# FIT_TCM_P1V0.net
KiCad netlist of a schematic drawn in Altium Designer
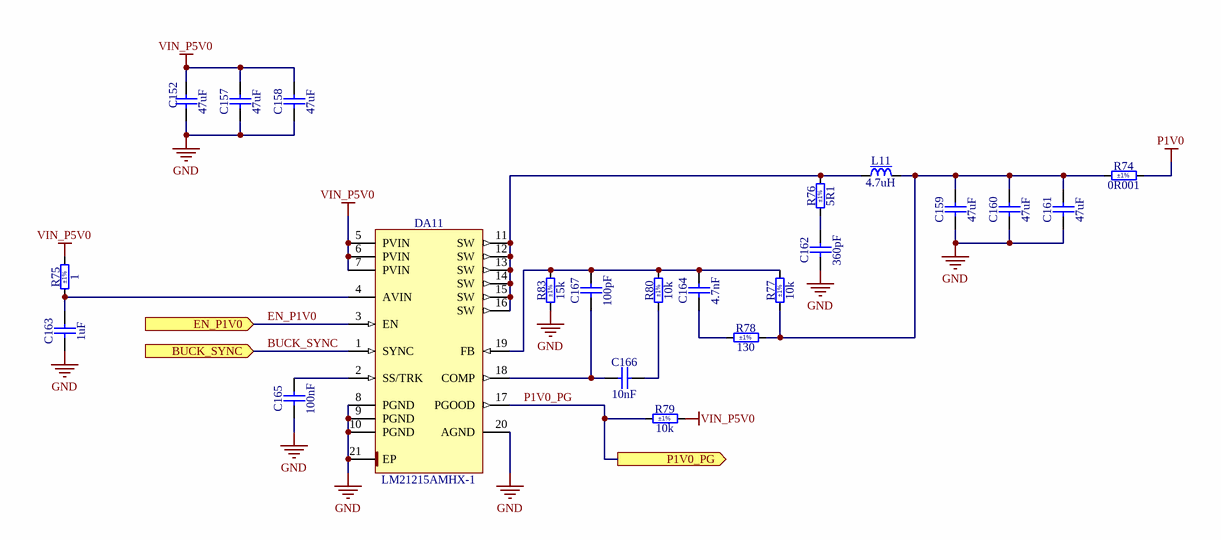
[diagram p0: FIT_TCM_P1V0.SchDoc]

(export (version "E")
  (design (tool "Eeschema 10.0.6"))
  (components
    (comp (ref "C152")
      (value "47uF")
      (footprint "CAPC3225X270N")
      (description "Non-polarised capacitor")
      (fields
        (field (name "PART NUMBER") "CC1210_47UF_16V_20%_X5R")
        (field (name "VOLTAGE") "16V")
        (field (name "AUTHOR") "CERN DEM MR")
      )
      (libsource (lib "Capacitors") (part "Capacitor - non polarized"))
    )
    (comp (ref "C157")
      (value "47uF")
      (footprint "CAPC3225X270N")
      (description "Non-polarised capacitor")
      (fields
        (field (name "PART NUMBER") "CC1210_47UF_16V_20%_X5R")
        (field (name "VOLTAGE") "16V")
        (field (name "AUTHOR") "CERN DEM MR")
      )
      (libsource (lib "Capacitors") (part "Capacitor - non polarized"))
    )
    (comp (ref "C158")
      (value "47uF")
      (footprint "CAPC3225X270N")
      (description "Non-polarised capacitor")
      (fields
        (field (name "PART NUMBER") "CC1210_47UF_16V_20%_X5R")
        (field (name "VOLTAGE") "16V")
        (field (name "AUTHOR") "CERN DEM MR")
      )
      (libsource (lib "Capacitors") (part "Capacitor - non polarized"))
    )
    (comp (ref "C159")
      (value "47uF")
      (footprint "CAPC3225X270N")
      (description "Non-polarised capacitor")
      (fields
        (field (name "PART NUMBER") "CC1210_47UF_16V_20%_X5R")
        (field (name "VOLTAGE") "16V")
        (field (name "AUTHOR") "CERN DEM MR")
      )
      (libsource (lib "Capacitors") (part "Capacitor - non polarized"))
    )
    (comp (ref "C160")
      (value "47uF")
      (footprint "CAPC3225X270N")
      (description "Non-polarised capacitor")
      (fields
        (field (name "PART NUMBER") "CC1210_47UF_16V_20%_X5R")
        (field (name "VOLTAGE") "16V")
        (field (name "AUTHOR") "CERN DEM MR")
      )
      (libsource (lib "Capacitors") (part "Capacitor - non polarized"))
    )
    (comp (ref "C161")
      (value "47uF")
      (footprint "CAPC3225X270N")
      (description "Non-polarised capacitor")
      (fields
        (field (name "PART NUMBER") "CC1210_47UF_16V_20%_X5R")
        (field (name "VOLTAGE") "16V")
        (field (name "AUTHOR") "CERN DEM MR")
      )
      (libsource (lib "Capacitors") (part "Capacitor - non polarized"))
    )
    (comp (ref "C162")
      (value "360pF")
      (footprint "CAPC2013X145N")
      (description "Non-polarised capacitor")
      (fields
        (field (name "PART NUMBER") "CC0805_360PF_50V_5%_C0G")
        (field (name "VOLTAGE") "50V")
        (field (name "AUTHOR") "CERN DEM HF")
      )
      (libsource (lib "Capacitors") (part "Capacitor - non polarized"))
    )
    (comp (ref "C163")
      (value "1uF")
      (footprint "CAPC2012X140N")
      (description "Non-polarised capacitor")
      (fields
        (field (name "PART NUMBER") "CC0805_1UF_25V_10%_X7R")
        (field (name "VOLTAGE") "25V")
        (field (name "AUTHOR") "CERN DEM JLC")
      )
      (libsource (lib "Capacitors") (part "Capacitor - non polarized"))
    )
    (comp (ref "C164")
      (value "4.7nF")
      (footprint "CAPC2012X135N")
      (description "Non-polarised capacitor")
      (fields
        (field (name "PART NUMBER") "CC0805_4.7NF_50V_10%_X7R")
        (field (name "VOLTAGE") "50V")
        (field (name "AUTHOR") "CERN DEM JLC")
      )
      (libsource (lib "Capacitors") (part "Capacitor - non polarized"))
    )
    (comp (ref "C165")
      (value "100nF")
      (footprint "CAPC2012X135N")
      (description "Non-polarised capacitor")
      (fields
        (field (name "PART NUMBER") "CC0805_100NF_50V_10%_X7R")
        (field (name "VOLTAGE") "50V")
        (field (name "AUTHOR") "CERN DEM JLC")
      )
      (libsource (lib "Capacitors") (part "Capacitor - non polarized"))
    )
    (comp (ref "C166")
      (value "10nF")
      (footprint "CAPC2012X135N")
      (description "Non-polarised capacitor")
      (fields
        (field (name "PART NUMBER") "CC0805_10NF_50V_10%_X7R")
        (field (name "VOLTAGE") "50V")
        (field (name "AUTHOR") "CERN DEM JLC")
      )
      (libsource (lib "Capacitors") (part "Capacitor - non polarized"))
    )
    (comp (ref "C167")
      (value "100pF")
      (footprint "CAPC2012X135N")
      (description "Non-polarised capacitor")
      (fields
        (field (name "PART NUMBER") "CC0805_100PF_50V_5%_NP0")
        (field (name "VOLTAGE") "50V")
        (field (name "AUTHOR") "CERN DEM JLC")
      )
      (libsource (lib "Capacitors") (part "Capacitor - non polarized"))
    )
    (comp (ref "DA11")
      (value "LM21215AMHX-1")
      (footprint "TEXAS_PWP0020AA")
      (description "2.95-V To 5.5-V, 12-A, Voltage-Mode Synchronous Buck Regulator with Frequency Synchronization")
      (fields (field (name "MANUFACTURER") "TEXAS INSTRUMENTS") (field (name "AUTHOR") "CERN DEM HF"))
      (libsource (lib "ICs And Semiconductors") (part "LM21215"))
    )
    (comp (ref "L11")
      (value "4.7uH")
      (footprint "INDM172170X700N")
      (description "Inductor With Core")
      (fields
        (field (name "PART NUMBER") "IND6767_4.7UH_20%_VISHAY_IHLP-6767GZ-11")
        (field (name "POWER") "30A")
        (field (name "AUTHOR") "CERN DEM HF")
      )
      (libsource (lib "Inductors & Transformers") (part "Inductor With Magnetic core"))
    )
    (comp (ref "R74")
      (value "0R001")
      (footprint "RESC_BOURNS_CRE2512_0R001-0R004")
      (description "Resistor - 1%")
      (fields
        (field (name "TOLERANCE") "±1%")
        (field (name "PART NUMBER") "R2512_0R001_1%_3W_50PPM_BOURNS_CRE2512")
        (field (name "POWER") "3W")
        (field (name "AUTHOR") "CERN DEM BC")
      )
      (libsource (lib "Resistors") (part "Resistor - 1%"))
    )
    (comp (ref "R75")
      (value "1")
      (footprint "RESC2012X60N")
      (description "Resistor - 1%")
      (fields
        (field (name "TOLERANCE") "±1%")
        (field (name "PART NUMBER") "R0805_1R_1%_0.125W_100PPM")
        (field (name "POWER") "0.125W")
        (field (name "AUTHOR") "CERN DEM HF")
      )
      (libsource (lib "Resistors") (part "Resistor - 1%"))
    )
    (comp (ref "R76")
      (value "5R1")
      (footprint "RESC2012X60N")
      (description "Resistor - 1%")
      (fields
        (field (name "TOLERANCE") "±1%")
        (field (name "PART NUMBER") "R0805_5R1_1%_0.125W_100PPM")
        (field (name "POWER") "0.125W")
        (field (name "AUTHOR") "CERN DEM HF")
      )
      (libsource (lib "Resistors") (part "Resistor - 1%"))
    )
    (comp (ref "R77")
      (value "10k")
      (footprint "RESC2012X60N")
      (description "Resistor - 1%")
      (fields
        (field (name "TOLERANCE") "±1%")
        (field (name "PART NUMBER") "R0805_10K_1%_0.125W_100PPM")
        (field (name "POWER") "0.125W")
        (field (name "AUTHOR") "CERN DEM JLC")
      )
      (libsource (lib "Resistors") (part "Resistor - 1%"))
    )
    (comp (ref "R78")
      (value "130")
      (footprint "RESC2012X60N")
      (description "Resistor - 1%")
      (fields
        (field (name "TOLERANCE") "±1%")
        (field (name "PART NUMBER") "R0805_130R_1%_0.125W_100PPM")
        (field (name "POWER") "0.125W")
        (field (name "AUTHOR") "CERN DEM JLC")
      )
      (libsource (lib "Resistors") (part "Resistor - 1%"))
    )
    (comp (ref "R79")
      (value "10k")
      (footprint "RESC2012X60N")
      (description "Resistor - 1%")
      (fields
        (field (name "TOLERANCE") "±1%")
        (field (name "PART NUMBER") "R0805_10K_1%_0.125W_100PPM")
        (field (name "POWER") "0.125W")
        (field (name "AUTHOR") "CERN DEM JLC")
      )
      (libsource (lib "Resistors") (part "Resistor - 1%"))
    )
    (comp (ref "R80")
      (value "10k")
      (footprint "RESC2012X60N")
      (description "Resistor - 1%")
      (fields
        (field (name "TOLERANCE") "±1%")
        (field (name "PART NUMBER") "R0805_10K_1%_0.125W_100PPM")
        (field (name "POWER") "0.125W")
        (field (name "AUTHOR") "CERN DEM JLC")
      )
      (libsource (lib "Resistors") (part "Resistor - 1%"))
    )
    (comp (ref "R83")
      (value "15k")
      (footprint "RESC2012X60N")
      (description "Resistor - 1%")
      (fields
        (field (name "TOLERANCE") "±1%")
        (field (name "PART NUMBER") "R0805_15K_1%_0.125W_100PPM")
        (field (name "POWER") "0.125W")
        (field (name "AUTHOR") "CERN DEM JLC")
      )
      (libsource (lib "Resistors") (part "Resistor - 1%"))
    )
  )
  (nets
    (net (code "1") (name "/BUCK_SYNC") (class "Default")
      (node (ref "DA11") (pin "1") (pinfunction "SYNC_1") (pintype "input"))
    )
    (net (code "2") (name "/EN_P1V0") (class "Default")
      (node (ref "DA11") (pin "3") (pinfunction "EN_3") (pintype "input"))
    )
    (net (code "3") (name "/P1V0_PG") (class "Default")
      (node (ref "DA11") (pin "17") (pinfunction "PGOOD_17") (pintype "output"))
      (node (ref "R79") (pin "1") (pinfunction "1_1") (pintype "passive"))
    )
    (net (code "4") (name "GND") (class "Default")
      (node (ref "C152") (pin "1") (pinfunction "1_1") (pintype "passive"))
      (node (ref "C157") (pin "1") (pinfunction "1_1") (pintype "passive"))
      (node (ref "C158") (pin "1") (pinfunction "1_1") (pintype "passive"))
      (node (ref "C159") (pin "1") (pinfunction "1_1") (pintype "passive"))
      (node (ref "C160") (pin "1") (pinfunction "1_1") (pintype "passive"))
      (node (ref "C161") (pin "1") (pinfunction "1_1") (pintype "passive"))
      (node (ref "C162") (pin "1") (pinfunction "1_1") (pintype "passive"))
      (node (ref "C163") (pin "1") (pinfunction "1_1") (pintype "passive"))
      (node (ref "C165") (pin "1") (pinfunction "1_1") (pintype "passive"))
      (node (ref "DA11") (pin "10") (pinfunction "PGND_10") (pintype "power_in"))
      (node (ref "DA11") (pin "20") (pinfunction "AGND_20") (pintype "power_in"))
      (node (ref "DA11") (pin "21") (pinfunction "EP_21") (pintype "power_in"))
      (node (ref "DA11") (pin "8") (pinfunction "PGND_8") (pintype "power_in"))
      (node (ref "DA11") (pin "9") (pinfunction "PGND_9") (pintype "power_in"))
      (node (ref "R83") (pin "1") (pinfunction "1_1") (pintype "passive"))
    )
    (net (code "5") (name "Net-(C159-Pad2)") (class "Default")
      (node (ref "C159") (pin "2") (pinfunction "2_2") (pintype "passive"))
      (node (ref "C160") (pin "2") (pinfunction "2_2") (pintype "passive"))
      (node (ref "C161") (pin "2") (pinfunction "2_2") (pintype "passive"))
      (node (ref "L11") (pin "2") (pinfunction "2_2") (pintype "passive"))
      (node (ref "R74") (pin "1") (pinfunction "1_1") (pintype "passive"))
      (node (ref "R77") (pin "1") (pinfunction "1_1") (pintype "passive"))
      (node (ref "R78") (pin "2") (pinfunction "2_2") (pintype "passive"))
    )
    (net (code "6") (name "Net-(C162-Pad2)") (class "Default")
      (node (ref "C162") (pin "2") (pinfunction "2_2") (pintype "passive"))
      (node (ref "R76") (pin "1") (pinfunction "1_1") (pintype "passive"))
    )
    (net (code "7") (name "Net-(C164-Pad1)") (class "Default")
      (node (ref "C164") (pin "1") (pinfunction "1_1") (pintype "passive"))
      (node (ref "R78") (pin "1") (pinfunction "1_1") (pintype "passive"))
    )
    (net (code "8") (name "Net-(C166-Pad2)") (class "Default")
      (node (ref "C166") (pin "2") (pinfunction "2_2") (pintype "passive"))
      (node (ref "R80") (pin "1") (pinfunction "1_1") (pintype "passive"))
    )
    (net (code "9") (name "Net-(DA11-AVIN)") (class "Default")
      (node (ref "C163") (pin "2") (pinfunction "2_2") (pintype "passive"))
      (node (ref "DA11") (pin "4") (pinfunction "AVIN_4") (pintype "power_in"))
      (node (ref "R75") (pin "1") (pinfunction "1_1") (pintype "passive"))
    )
    (net (code "10") (name "Net-(DA11-COMP)") (class "Default")
      (node (ref "C166") (pin "1") (pinfunction "1_1") (pintype "passive"))
      (node (ref "C167") (pin "1") (pinfunction "1_1") (pintype "passive"))
      (node (ref "DA11") (pin "18") (pinfunction "COMP_18") (pintype "output"))
    )
    (net (code "11") (name "Net-(DA11-FB)") (class "Default")
      (node (ref "C164") (pin "2") (pinfunction "2_2") (pintype "passive"))
      (node (ref "C167") (pin "2") (pinfunction "2_2") (pintype "passive"))
      (node (ref "DA11") (pin "19") (pinfunction "FB_19") (pintype "input"))
      (node (ref "R77") (pin "2") (pinfunction "2_2") (pintype "passive"))
      (node (ref "R80") (pin "2") (pinfunction "2_2") (pintype "passive"))
      (node (ref "R83") (pin "2") (pinfunction "2_2") (pintype "passive"))
    )
    (net (code "12") (name "Net-(DA11-SS{slash}TRK)") (class "Default")
      (node (ref "C165") (pin "2") (pinfunction "2_2") (pintype "passive"))
      (node (ref "DA11") (pin "2") (pinfunction "SS/TRK_2") (pintype "input"))
    )
    (net (code "13") (name "Net-(DA11-SW-Pad11)") (class "Default")
      (node (ref "DA11") (pin "11") (pinfunction "SW_11") (pintype "output"))
      (node (ref "DA11") (pin "12") (pinfunction "SW_12") (pintype "output"))
      (node (ref "DA11") (pin "13") (pinfunction "SW_13") (pintype "output"))
      (node (ref "DA11") (pin "14") (pinfunction "SW_14") (pintype "output"))
      (node (ref "DA11") (pin "15") (pinfunction "SW_15") (pintype "output"))
      (node (ref "DA11") (pin "16") (pinfunction "SW_16") (pintype "output"))
      (node (ref "L11") (pin "1") (pinfunction "1_1") (pintype "passive"))
      (node (ref "R76") (pin "2") (pinfunction "2_2") (pintype "passive"))
    )
    (net (code "14") (name "P1V0") (class "Default")
      (node (ref "R74") (pin "2") (pinfunction "2_2") (pintype "passive"))
    )
    (net (code "15") (name "VIN_P5V0") (class "Default")
      (node (ref "C152") (pin "2") (pinfunction "2_2") (pintype "passive"))
      (node (ref "C157") (pin "2") (pinfunction "2_2") (pintype "passive"))
      (node (ref "C158") (pin "2") (pinfunction "2_2") (pintype "passive"))
      (node (ref "DA11") (pin "5") (pinfunction "PVIN_5") (pintype "power_in"))
      (node (ref "DA11") (pin "6") (pinfunction "PVIN_6") (pintype "power_in"))
      (node (ref "DA11") (pin "7") (pinfunction "PVIN_7") (pintype "power_in"))
      (node (ref "R75") (pin "2") (pinfunction "2_2") (pintype "passive"))
      (node (ref "R79") (pin "2") (pinfunction "2_2") (pintype "passive"))
    )
  )
)
